# servis.net
KiCad netlist of a schematic drawn in EAGLE
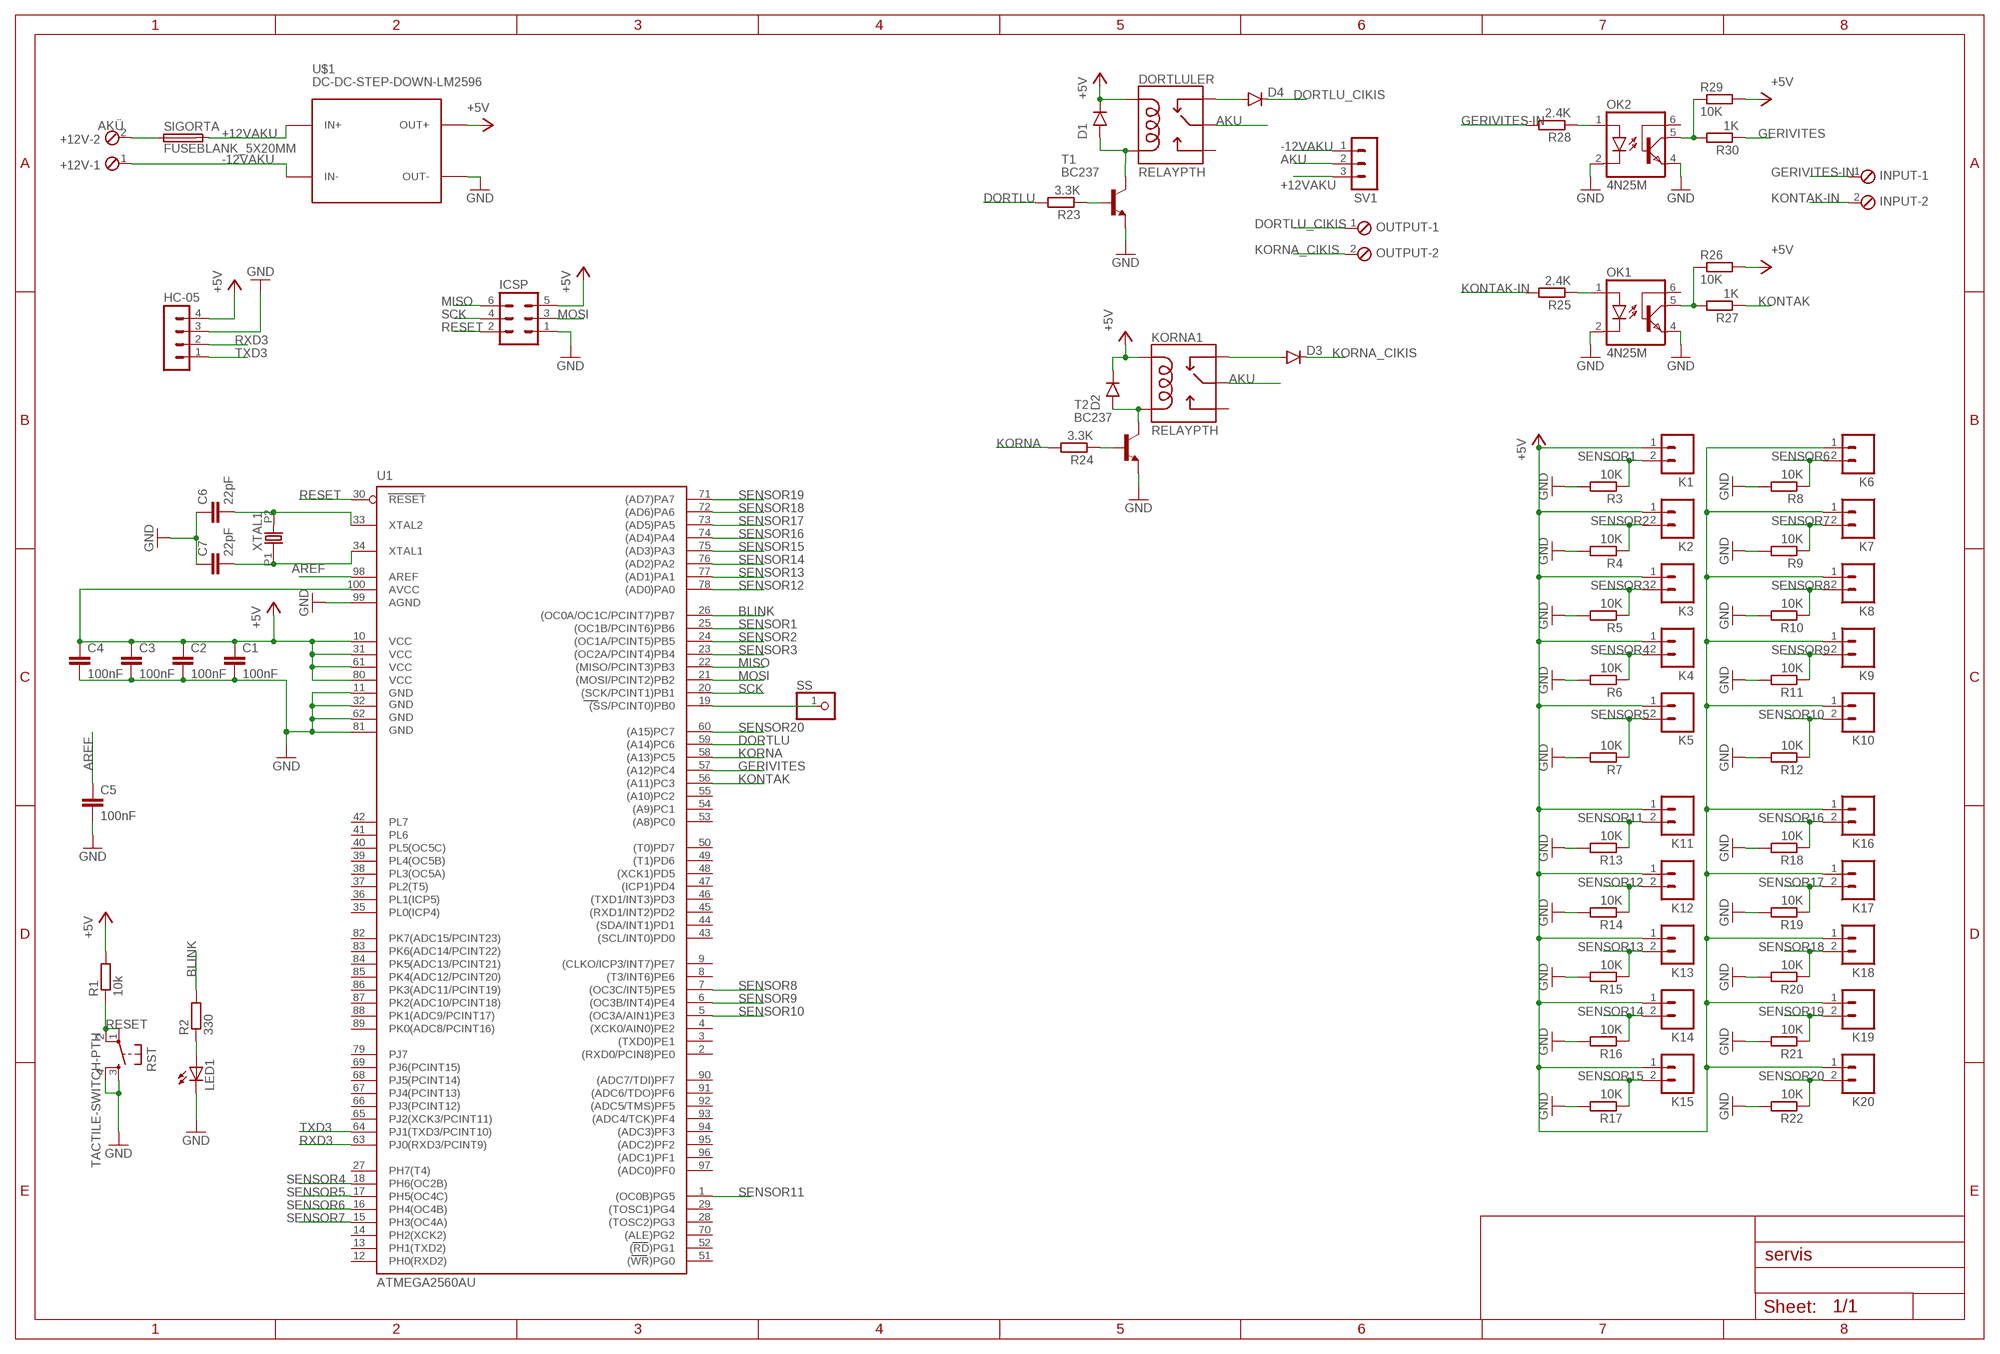
[diagram p0: schematic, sheet 1]

(export (version "E")
  (design (tool "Eeschema 10.0.6"))
  (components
    (comp (ref "+12V")
      (value "AKÜ")
      (footprint "eagle-import:2POL254")
      (libsource (lib "eagle-import") (part "MPT2"))
    )
    (comp (ref "C1")
      (value "100nF")
      (footprint "eagle-import:SPARKFUN_0805")
      (libsource (lib "eagle-import") (part "SPARKFUN_CAP0805"))
    )
    (comp (ref "C2")
      (value "100nF")
      (footprint "eagle-import:SPARKFUN_0805")
      (libsource (lib "eagle-import") (part "SPARKFUN_CAP0805"))
    )
    (comp (ref "C3")
      (value "100nF")
      (footprint "eagle-import:SPARKFUN_0805")
      (libsource (lib "eagle-import") (part "SPARKFUN_CAP0805"))
    )
    (comp (ref "C4")
      (value "100nF")
      (footprint "eagle-import:SPARKFUN_0805")
      (libsource (lib "eagle-import") (part "SPARKFUN_CAP0805"))
    )
    (comp (ref "C5")
      (value "100nF")
      (footprint "eagle-import:SPARKFUN_0805")
      (libsource (lib "eagle-import") (part "SPARKFUN_CAP0805"))
    )
    (comp (ref "C6")
      (value "22pF")
      (footprint "eagle-import:SPARKFUN_0805")
      (libsource (lib "eagle-import") (part "SPARKFUN_CAP0805"))
    )
    (comp (ref "C7")
      (value "22pF")
      (footprint "eagle-import:SPARKFUN_0805")
      (libsource (lib "eagle-import") (part "SPARKFUN_CAP0805"))
    )
    (comp (ref "D1")
      (value "1N4001")
      (footprint "eagle-import:DO41-10")
      (libsource (lib "eagle-import") (part "1N4001"))
    )
    (comp (ref "D2")
      (value "1N4001")
      (footprint "eagle-import:DO41-10")
      (libsource (lib "eagle-import") (part "1N4001"))
    )
    (comp (ref "D3")
      (value "DIODEPTH")
      (footprint "eagle-import:DIODE-1N4001")
      (libsource (lib "eagle-import") (part "DIODEPTH"))
    )
    (comp (ref "D4")
      (value "DIODEPTH")
      (footprint "eagle-import:DIODE-1N4001")
      (libsource (lib "eagle-import") (part "DIODEPTH"))
    )
    (comp (ref "DORTLULER")
      (value "RELAYPTH")
      (footprint "eagle-import:SRD-05VDC-SL-C")
      (libsource (lib "eagle-import") (part "RELAYPTH"))
    )
    (comp (ref "HC-05")
      (value "MA04-1")
      (footprint "eagle-import:MA04-1")
      (libsource (lib "eagle-import") (part "MA04-1"))
    )
    (comp (ref "ICSP")
      (value "MA03-2")
      (footprint "eagle-import:MA03-2")
      (libsource (lib "eagle-import") (part "MA03-2"))
    )
    (comp (ref "INPUT")
      (value "AKÜ")
      (footprint "eagle-import:2POL254")
      (libsource (lib "eagle-import") (part "MPT2"))
    )
    (comp (ref "K1")
      (value "SPARKFUN_M02-JST-2-PTH-NO_SILK")
      (footprint "eagle-import:SPARKFUN_JST-2-PTH-NS")
      (libsource (lib "eagle-import") (part "SPARKFUN_M02-JST-2-PTH-NO_SILK"))
    )
    (comp (ref "K2")
      (value "SPARKFUN_M02-JST-2-PTH-NO_SILK")
      (footprint "eagle-import:SPARKFUN_JST-2-PTH-NS")
      (libsource (lib "eagle-import") (part "SPARKFUN_M02-JST-2-PTH-NO_SILK"))
    )
    (comp (ref "K3")
      (value "SPARKFUN_M02-JST-2-PTH-NO_SILK")
      (footprint "eagle-import:SPARKFUN_JST-2-PTH-NS")
      (libsource (lib "eagle-import") (part "SPARKFUN_M02-JST-2-PTH-NO_SILK"))
    )
    (comp (ref "K4")
      (value "SPARKFUN_M02-JST-2-PTH-NO_SILK")
      (footprint "eagle-import:SPARKFUN_JST-2-PTH-NS")
      (libsource (lib "eagle-import") (part "SPARKFUN_M02-JST-2-PTH-NO_SILK"))
    )
    (comp (ref "K5")
      (value "SPARKFUN_M02-JST-2-PTH-NO_SILK")
      (footprint "eagle-import:SPARKFUN_JST-2-PTH-NS")
      (libsource (lib "eagle-import") (part "SPARKFUN_M02-JST-2-PTH-NO_SILK"))
    )
    (comp (ref "K6")
      (value "SPARKFUN_M02-JST-2-PTH-NO_SILK")
      (footprint "eagle-import:SPARKFUN_JST-2-PTH-NS")
      (libsource (lib "eagle-import") (part "SPARKFUN_M02-JST-2-PTH-NO_SILK"))
    )
    (comp (ref "K7")
      (value "SPARKFUN_M02-JST-2-PTH-NO_SILK")
      (footprint "eagle-import:SPARKFUN_JST-2-PTH-NS")
      (libsource (lib "eagle-import") (part "SPARKFUN_M02-JST-2-PTH-NO_SILK"))
    )
    (comp (ref "K8")
      (value "SPARKFUN_M02-JST-2-PTH-NO_SILK")
      (footprint "eagle-import:SPARKFUN_JST-2-PTH-NS")
      (libsource (lib "eagle-import") (part "SPARKFUN_M02-JST-2-PTH-NO_SILK"))
    )
    (comp (ref "K9")
      (value "SPARKFUN_M02-JST-2-PTH-NO_SILK")
      (footprint "eagle-import:SPARKFUN_JST-2-PTH-NS")
      (libsource (lib "eagle-import") (part "SPARKFUN_M02-JST-2-PTH-NO_SILK"))
    )
    (comp (ref "K10")
      (value "SPARKFUN_M02-JST-2-PTH-NO_SILK")
      (footprint "eagle-import:SPARKFUN_JST-2-PTH-NS")
      (libsource (lib "eagle-import") (part "SPARKFUN_M02-JST-2-PTH-NO_SILK"))
    )
    (comp (ref "K11")
      (value "SPARKFUN_M02-JST-2-PTH-NO_SILK")
      (footprint "eagle-import:SPARKFUN_JST-2-PTH-NS")
      (libsource (lib "eagle-import") (part "SPARKFUN_M02-JST-2-PTH-NO_SILK"))
    )
    (comp (ref "K12")
      (value "SPARKFUN_M02-JST-2-PTH-NO_SILK")
      (footprint "eagle-import:SPARKFUN_JST-2-PTH-NS")
      (libsource (lib "eagle-import") (part "SPARKFUN_M02-JST-2-PTH-NO_SILK"))
    )
    (comp (ref "K13")
      (value "SPARKFUN_M02-JST-2-PTH-NO_SILK")
      (footprint "eagle-import:SPARKFUN_JST-2-PTH-NS")
      (libsource (lib "eagle-import") (part "SPARKFUN_M02-JST-2-PTH-NO_SILK"))
    )
    (comp (ref "K14")
      (value "SPARKFUN_M02-JST-2-PTH-NO_SILK")
      (footprint "eagle-import:SPARKFUN_JST-2-PTH-NS")
      (libsource (lib "eagle-import") (part "SPARKFUN_M02-JST-2-PTH-NO_SILK"))
    )
    (comp (ref "K15")
      (value "SPARKFUN_M02-JST-2-PTH-NO_SILK")
      (footprint "eagle-import:SPARKFUN_JST-2-PTH-NS")
      (libsource (lib "eagle-import") (part "SPARKFUN_M02-JST-2-PTH-NO_SILK"))
    )
    (comp (ref "K16")
      (value "SPARKFUN_M02-JST-2-PTH-NO_SILK")
      (footprint "eagle-import:SPARKFUN_JST-2-PTH-NS")
      (libsource (lib "eagle-import") (part "SPARKFUN_M02-JST-2-PTH-NO_SILK"))
    )
    (comp (ref "K17")
      (value "SPARKFUN_M02-JST-2-PTH-NO_SILK")
      (footprint "eagle-import:SPARKFUN_JST-2-PTH-NS")
      (libsource (lib "eagle-import") (part "SPARKFUN_M02-JST-2-PTH-NO_SILK"))
    )
    (comp (ref "K18")
      (value "SPARKFUN_M02-JST-2-PTH-NO_SILK")
      (footprint "eagle-import:SPARKFUN_JST-2-PTH-NS")
      (libsource (lib "eagle-import") (part "SPARKFUN_M02-JST-2-PTH-NO_SILK"))
    )
    (comp (ref "K19")
      (value "SPARKFUN_M02-JST-2-PTH-NO_SILK")
      (footprint "eagle-import:SPARKFUN_JST-2-PTH-NS")
      (libsource (lib "eagle-import") (part "SPARKFUN_M02-JST-2-PTH-NO_SILK"))
    )
    (comp (ref "K20")
      (value "SPARKFUN_M02-JST-2-PTH-NO_SILK")
      (footprint "eagle-import:SPARKFUN_JST-2-PTH-NS")
      (libsource (lib "eagle-import") (part "SPARKFUN_M02-JST-2-PTH-NO_SILK"))
    )
    (comp (ref "KORNA1")
      (value "RELAYPTH")
      (footprint "eagle-import:SRD-05VDC-SL-C")
      (libsource (lib "eagle-import") (part "RELAYPTH"))
    )
    (comp (ref "LED1")
      (value "SPARKFUN_LED3MM")
      (footprint "eagle-import:SPARKFUN_LED3MM")
      (libsource (lib "eagle-import") (part "SPARKFUN_LED3MM"))
    )
    (comp (ref "OK1")
      (value "4N25M")
      (footprint "eagle-import:DIL06")
      (fields (field (name "MPN") "4N25-M"))
      (libsource (lib "eagle-import") (part "4N?M25"))
    )
    (comp (ref "OK2")
      (value "4N25M")
      (footprint "eagle-import:DIL06")
      (fields (field (name "MPN") "4N25-M"))
      (libsource (lib "eagle-import") (part "4N?M25"))
    )
    (comp (ref "OUTPUT")
      (value "AKÜ")
      (footprint "eagle-import:2POL254")
      (libsource (lib "eagle-import") (part "MPT2"))
    )
    (comp (ref "R1")
      (value "10k")
      (footprint "eagle-import:R805")
      (libsource (lib "eagle-import") (part "RESISTOR-0805R805"))
    )
    (comp (ref "R2")
      (value "330")
      (footprint "eagle-import:R805")
      (libsource (lib "eagle-import") (part "RESISTOR-0805R805"))
    )
    (comp (ref "R3")
      (value "10K")
      (footprint "eagle-import:R805")
      (libsource (lib "eagle-import") (part "RESISTOR-0805R805"))
    )
    (comp (ref "R4")
      (value "10K")
      (footprint "eagle-import:R805")
      (libsource (lib "eagle-import") (part "RESISTOR-0805R805"))
    )
    (comp (ref "R5")
      (value "10K")
      (footprint "eagle-import:R805")
      (libsource (lib "eagle-import") (part "RESISTOR-0805R805"))
    )
    (comp (ref "R6")
      (value "10K")
      (footprint "eagle-import:R805")
      (libsource (lib "eagle-import") (part "RESISTOR-0805R805"))
    )
    (comp (ref "R7")
      (value "10K")
      (footprint "eagle-import:R805")
      (libsource (lib "eagle-import") (part "RESISTOR-0805R805"))
    )
    (comp (ref "R8")
      (value "10K")
      (footprint "eagle-import:R805")
      (libsource (lib "eagle-import") (part "RESISTOR-0805R805"))
    )
    (comp (ref "R9")
      (value "10K")
      (footprint "eagle-import:R805")
      (libsource (lib "eagle-import") (part "RESISTOR-0805R805"))
    )
    (comp (ref "R10")
      (value "10K")
      (footprint "eagle-import:R805")
      (libsource (lib "eagle-import") (part "RESISTOR-0805R805"))
    )
    (comp (ref "R11")
      (value "10K")
      (footprint "eagle-import:R805")
      (libsource (lib "eagle-import") (part "RESISTOR-0805R805"))
    )
    (comp (ref "R12")
      (value "10K")
      (footprint "eagle-import:R805")
      (libsource (lib "eagle-import") (part "RESISTOR-0805R805"))
    )
    (comp (ref "R13")
      (value "10K")
      (footprint "eagle-import:R805")
      (libsource (lib "eagle-import") (part "RESISTOR-0805R805"))
    )
    (comp (ref "R14")
      (value "10K")
      (footprint "eagle-import:R805")
      (libsource (lib "eagle-import") (part "RESISTOR-0805R805"))
    )
    (comp (ref "R15")
      (value "10K")
      (footprint "eagle-import:R805")
      (libsource (lib "eagle-import") (part "RESISTOR-0805R805"))
    )
    (comp (ref "R16")
      (value "10K")
      (footprint "eagle-import:R805")
      (libsource (lib "eagle-import") (part "RESISTOR-0805R805"))
    )
    (comp (ref "R17")
      (value "10K")
      (footprint "eagle-import:R805")
      (libsource (lib "eagle-import") (part "RESISTOR-0805R805"))
    )
    (comp (ref "R18")
      (value "10K")
      (footprint "eagle-import:R805")
      (libsource (lib "eagle-import") (part "RESISTOR-0805R805"))
    )
    (comp (ref "R19")
      (value "10K")
      (footprint "eagle-import:R805")
      (libsource (lib "eagle-import") (part "RESISTOR-0805R805"))
    )
    (comp (ref "R20")
      (value "10K")
      (footprint "eagle-import:R805")
      (libsource (lib "eagle-import") (part "RESISTOR-0805R805"))
    )
    (comp (ref "R21")
      (value "10K")
      (footprint "eagle-import:R805")
      (libsource (lib "eagle-import") (part "RESISTOR-0805R805"))
    )
    (comp (ref "R22")
      (value "10K")
      (footprint "eagle-import:R805")
      (libsource (lib "eagle-import") (part "RESISTOR-0805R805"))
    )
    (comp (ref "R23")
      (value "3.3K")
      (footprint "eagle-import:R805")
      (libsource (lib "eagle-import") (part "RESISTOR-0805R805"))
    )
    (comp (ref "R24")
      (value "3.3K")
      (footprint "eagle-import:R805")
      (libsource (lib "eagle-import") (part "RESISTOR-0805R805"))
    )
    (comp (ref "R25")
      (value "2.4K")
      (footprint "eagle-import:R805")
      (libsource (lib "eagle-import") (part "RESISTOR-0805R805"))
    )
    (comp (ref "R26")
      (value "10K")
      (footprint "eagle-import:R805")
      (libsource (lib "eagle-import") (part "RESISTOR-0805R805"))
    )
    (comp (ref "R27")
      (value "1K")
      (footprint "eagle-import:R805")
      (libsource (lib "eagle-import") (part "RESISTOR-0805R805"))
    )
    (comp (ref "R28")
      (value "2.4K")
      (footprint "eagle-import:R805")
      (libsource (lib "eagle-import") (part "RESISTOR-0805R805"))
    )
    (comp (ref "R29")
      (value "10K")
      (footprint "eagle-import:R805")
      (libsource (lib "eagle-import") (part "RESISTOR-0805R805"))
    )
    (comp (ref "R30")
      (value "1K")
      (footprint "eagle-import:R805")
      (libsource (lib "eagle-import") (part "RESISTOR-0805R805"))
    )
    (comp (ref "RST")
      (value "TACTILE-SWITCH-PTH")
      (footprint "eagle-import:TAC-SWITCH-PTH")
      (libsource (lib "eagle-import") (part "TACTILE-SWITCH-PTH"))
    )
    (comp (ref "SIGORTA")
      (value "FUSEBLANK_5X20MM")
      (footprint "eagle-import:FUSE_HOLDER_5X20MM")
      (libsource (lib "eagle-import") (part "FUSEBLANK_5X20MM"))
    )
    (comp (ref "SS")
      (value "PINHD-1X1")
      (footprint "eagle-import:1X01")
      (libsource (lib "eagle-import") (part "PINHD-1X1"))
    )
    (comp (ref "SV1")
      (value "MA03-1")
      (footprint "eagle-import:MA03-1")
      (libsource (lib "eagle-import") (part "MA03-1"))
    )
    (comp (ref "T1")
      (value "BC237")
      (footprint "eagle-import:TO92")
      (libsource (lib "eagle-import") (part "BC237"))
    )
    (comp (ref "T2")
      (value "BC237")
      (footprint "eagle-import:TO92")
      (libsource (lib "eagle-import") (part "BC237"))
    )
    (comp (ref "U$1")
      (value "DC-DC-STEP-DOWN-LM2596")
      (footprint "eagle-import:DC-DC-STEP-DOWN-LM2596")
      (libsource (lib "eagle-import") (part "DC-DC-STEP-DOWN-LM2596"))
    )
    (comp (ref "U1")
      (value "ATMEGA2560AU")
      (footprint "eagle-import:TQFP100")
      (libsource (lib "eagle-import") (part "ATMEGA2560AU"))
    )
    (comp (ref "XTAL1")
      (value "OSC-XTAL-HC-49U-PTH")
      (footprint "eagle-import:HC-49U-PTH")
      (libsource (lib "eagle-import") (part "OSC-XTAL-HC-49U-PTH"))
    )
  )
  (nets
    (net (code "1") (name "+5V") (class "Default")
      (node (ref "C1") (pin "1") (pinfunction "1_1") (pintype "passive"))
      (node (ref "C2") (pin "1") (pinfunction "1_1") (pintype "passive"))
      (node (ref "C3") (pin "1") (pinfunction "1_1") (pintype "passive"))
      (node (ref "C4") (pin "1") (pinfunction "1_1") (pintype "passive"))
      (node (ref "D1") (pin "C") (pinfunction "CATHODE_C") (pintype "passive"))
      (node (ref "D2") (pin "C") (pinfunction "CATHODE_C") (pintype "passive"))
      (node (ref "DORTLULER") (pin "COIL1") (pinfunction "COIL1_COIL1") (pintype "bidirectional"))
      (node (ref "HC-05") (pin "4") (pinfunction "4_4") (pintype "passive"))
      (node (ref "ICSP") (pin "5") (pinfunction "5_5") (pintype "passive"))
      (node (ref "K1") (pin "1") (pinfunction "1_1") (pintype "passive"))
      (node (ref "K10") (pin "1") (pinfunction "1_1") (pintype "passive"))
      (node (ref "K11") (pin "1") (pinfunction "1_1") (pintype "passive"))
      (node (ref "K12") (pin "1") (pinfunction "1_1") (pintype "passive"))
      (node (ref "K13") (pin "1") (pinfunction "1_1") (pintype "passive"))
      (node (ref "K14") (pin "1") (pinfunction "1_1") (pintype "passive"))
      (node (ref "K15") (pin "1") (pinfunction "1_1") (pintype "passive"))
      (node (ref "K16") (pin "1") (pinfunction "1_1") (pintype "passive"))
      (node (ref "K17") (pin "1") (pinfunction "1_1") (pintype "passive"))
      (node (ref "K18") (pin "1") (pinfunction "1_1") (pintype "passive"))
      (node (ref "K19") (pin "1") (pinfunction "1_1") (pintype "passive"))
      (node (ref "K2") (pin "1") (pinfunction "1_1") (pintype "passive"))
      (node (ref "K20") (pin "1") (pinfunction "1_1") (pintype "passive"))
      (node (ref "K3") (pin "1") (pinfunction "1_1") (pintype "passive"))
      (node (ref "K4") (pin "1") (pinfunction "1_1") (pintype "passive"))
      (node (ref "K5") (pin "1") (pinfunction "1_1") (pintype "passive"))
      (node (ref "K6") (pin "1") (pinfunction "1_1") (pintype "passive"))
      (node (ref "K7") (pin "1") (pinfunction "1_1") (pintype "passive"))
      (node (ref "K8") (pin "1") (pinfunction "1_1") (pintype "passive"))
      (node (ref "K9") (pin "1") (pinfunction "1_1") (pintype "passive"))
      (node (ref "KORNA1") (pin "COIL1") (pinfunction "COIL1_COIL1") (pintype "bidirectional"))
      (node (ref "R1") (pin "2") (pinfunction "2_2") (pintype "passive"))
      (node (ref "R26") (pin "2") (pinfunction "2_2") (pintype "passive"))
      (node (ref "R29") (pin "2") (pinfunction "2_2") (pintype "passive"))
      (node (ref "U$1") (pin "OUT+") (pinfunction "OUT+_OUT+") (pintype "bidirectional"))
      (node (ref "U1") (pin "10") (pinfunction "VCC_10") (pintype "power_in"))
      (node (ref "U1") (pin "100") (pinfunction "AVCC_100") (pintype "power_in"))
      (node (ref "U1") (pin "31") (pinfunction "VCC1_31") (pintype "power_in"))
      (node (ref "U1") (pin "61") (pinfunction "VCC2_61") (pintype "power_in"))
      (node (ref "U1") (pin "80") (pinfunction "VCC3_80") (pintype "power_in"))
    )
    (net (code "2") (name "/+12VAKU") (class "Default")
      (node (ref "SIGORTA") (pin "2") (pinfunction "2_2") (pintype "passive"))
      (node (ref "SV1") (pin "3") (pinfunction "3_3") (pintype "passive"))
      (node (ref "U$1") (pin "IN+") (pinfunction "IN+_IN+") (pintype "bidirectional"))
    )
    (net (code "3") (name "/-12VAKU") (class "Default")
      (node (ref "+12V") (pin "1") (pinfunction "1_1") (pintype "passive"))
      (node (ref "SV1") (pin "1") (pinfunction "1_1") (pintype "passive"))
      (node (ref "U$1") (pin "IN-") (pinfunction "IN-_IN-") (pintype "bidirectional"))
    )
    (net (code "4") (name "/AKU") (class "Default")
      (node (ref "DORTLULER") (pin "SWCOMMON") (pinfunction "SWCOMMON_SWCOMMON") (pintype "bidirectional"))
      (node (ref "KORNA1") (pin "SWCOMMON") (pinfunction "SWCOMMON_SWCOMMON") (pintype "bidirectional"))
      (node (ref "SV1") (pin "2") (pinfunction "2_2") (pintype "passive"))
    )
    (net (code "5") (name "/AREF") (class "Default")
      (node (ref "C5") (pin "1") (pinfunction "1_1") (pintype "passive"))
      (node (ref "U1") (pin "98") (pinfunction "AREF_98") (pintype "bidirectional"))
    )
    (net (code "6") (name "/BLINK") (class "Default")
      (node (ref "R2") (pin "2") (pinfunction "2_2") (pintype "passive"))
      (node (ref "U1") (pin "26") (pinfunction "(OC0A/OC1C/PCINT7)PB7_26") (pintype "bidirectional"))
    )
    (net (code "7") (name "/DORTLU") (class "Default")
      (node (ref "R23") (pin "2") (pinfunction "2_2") (pintype "passive"))
      (node (ref "U1") (pin "59") (pinfunction "(A14)PC6_59") (pintype "bidirectional"))
    )
    (net (code "8") (name "/DORTLU_CIKIS") (class "Default")
      (node (ref "D4") (pin "C") (pinfunction "C_C") (pintype "passive"))
      (node (ref "OUTPUT") (pin "1") (pinfunction "1_1") (pintype "passive"))
    )
    (net (code "9") (name "/GERIVITES") (class "Default")
      (node (ref "R30") (pin "1") (pinfunction "1_1") (pintype "passive"))
      (node (ref "U1") (pin "57") (pinfunction "(A12)PC4_57") (pintype "bidirectional"))
    )
    (net (code "10") (name "/GERIVITES-IN") (class "Default")
      (node (ref "INPUT") (pin "1") (pinfunction "1_1") (pintype "passive"))
      (node (ref "R28") (pin "2") (pinfunction "2_2") (pintype "passive"))
    )
    (net (code "11") (name "/KONTAK") (class "Default")
      (node (ref "R27") (pin "1") (pinfunction "1_1") (pintype "passive"))
      (node (ref "U1") (pin "56") (pinfunction "(A11)PC3_56") (pintype "bidirectional"))
    )
    (net (code "12") (name "/KONTAK-IN") (class "Default")
      (node (ref "INPUT") (pin "2") (pinfunction "1_2") (pintype "passive"))
      (node (ref "R25") (pin "2") (pinfunction "2_2") (pintype "passive"))
    )
    (net (code "13") (name "/KORNA") (class "Default")
      (node (ref "R24") (pin "2") (pinfunction "2_2") (pintype "passive"))
      (node (ref "U1") (pin "58") (pinfunction "(A13)PC5_58") (pintype "bidirectional"))
    )
    (net (code "14") (name "/KORNA_CIKIS") (class "Default")
      (node (ref "D3") (pin "C") (pinfunction "C_C") (pintype "passive"))
      (node (ref "OUTPUT") (pin "2") (pinfunction "1_2") (pintype "passive"))
    )
    (net (code "15") (name "/MISO") (class "Default")
      (node (ref "ICSP") (pin "6") (pinfunction "6_6") (pintype "passive"))
      (node (ref "U1") (pin "22") (pinfunction "(MISO/PCINT3)PB3_22") (pintype "bidirectional"))
    )
    (net (code "16") (name "/MOSI") (class "Default")
      (node (ref "ICSP") (pin "3") (pinfunction "3_3") (pintype "passive"))
      (node (ref "U1") (pin "21") (pinfunction "(MOSI/PCINT2)PB2_21") (pintype "bidirectional"))
    )
    (net (code "17") (name "/RESET") (class "Default")
      (node (ref "ICSP") (pin "2") (pinfunction "2_2") (pintype "passive"))
      (node (ref "R1") (pin "1") (pinfunction "1_1") (pintype "passive"))
      (node (ref "RST") (pin "1") (pinfunction "1_1") (pintype "passive"))
      (node (ref "RST") (pin "2") (pinfunction "2_2") (pintype "passive"))
      (node (ref "U1") (pin "30") (pinfunction "RESET_30") (pintype "input"))
    )
    (net (code "18") (name "/RXD3") (class "Default")
      (node (ref "HC-05") (pin "2") (pinfunction "2_2") (pintype "passive"))
      (node (ref "U1") (pin "63") (pinfunction "PJ0(RXD3/PCINT9)_63") (pintype "bidirectional"))
    )
    (net (code "19") (name "/SCK") (class "Default")
      (node (ref "ICSP") (pin "4") (pinfunction "4_4") (pintype "passive"))
      (node (ref "U1") (pin "20") (pinfunction "(SCK/PCINT1)PB1_20") (pintype "bidirectional"))
    )
    (net (code "20") (name "/SENSOR1") (class "Default")
      (node (ref "K1") (pin "2") (pinfunction "2_2") (pintype "passive"))
      (node (ref "R3") (pin "1") (pinfunction "1_1") (pintype "passive"))
      (node (ref "U1") (pin "25") (pinfunction "(OC1B/PCINT6)PB6_25") (pintype "bidirectional"))
    )
    (net (code "21") (name "/SENSOR2") (class "Default")
      (node (ref "K2") (pin "2") (pinfunction "2_2") (pintype "passive"))
      (node (ref "R4") (pin "1") (pinfunction "1_1") (pintype "passive"))
      (node (ref "U1") (pin "24") (pinfunction "(OC1A/PCINT5)PB5_24") (pintype "bidirectional"))
    )
    (net (code "22") (name "/SENSOR3") (class "Default")
      (node (ref "K3") (pin "2") (pinfunction "2_2") (pintype "passive"))
      (node (ref "R5") (pin "1") (pinfunction "1_1") (pintype "passive"))
      (node (ref "U1") (pin "23") (pinfunction "(OC2A/PCINT4)PB4_23") (pintype "bidirectional"))
    )
    (net (code "23") (name "/SENSOR4") (class "Default")
      (node (ref "K4") (pin "2") (pinfunction "2_2") (pintype "passive"))
      (node (ref "R6") (pin "1") (pinfunction "1_1") (pintype "passive"))
      (node (ref "U1") (pin "18") (pinfunction "PH6(OC2B)_18") (pintype "bidirectional"))
    )
    (net (code "24") (name "/SENSOR5") (class "Default")
      (node (ref "K5") (pin "2") (pinfunction "2_2") (pintype "passive"))
      (node (ref "R7") (pin "1") (pinfunction "1_1") (pintype "passive"))
      (node (ref "U1") (pin "17") (pinfunction "PH5(OC4C)_17") (pintype "bidirectional"))
    )
    (net (code "25") (name "/SENSOR6") (class "Default")
      (node (ref "K6") (pin "2") (pinfunction "2_2") (pintype "passive"))
      (node (ref "R8") (pin "1") (pinfunction "1_1") (pintype "passive"))
      (node (ref "U1") (pin "16") (pinfunction "PH4(OC4B)_16") (pintype "bidirectional"))
    )
    (net (code "26") (name "/SENSOR7") (class "Default")
      (node (ref "K7") (pin "2") (pinfunction "2_2") (pintype "passive"))
      (node (ref "R9") (pin "1") (pinfunction "1_1") (pintype "passive"))
      (node (ref "U1") (pin "15") (pinfunction "PH3(OC4A)_15") (pintype "bidirectional"))
    )
    (net (code "27") (name "/SENSOR8") (class "Default")
      (node (ref "K8") (pin "2") (pinfunction "2_2") (pintype "passive"))
      (node (ref "R10") (pin "1") (pinfunction "1_1") (pintype "passive"))
      (node (ref "U1") (pin "7") (pinfunction "(OC3C/INT5)PE5_7") (pintype "bidirectional"))
    )
    (net (code "28") (name "/SENSOR9") (class "Default")
      (node (ref "K9") (pin "2") (pinfunction "2_2") (pintype "passive"))
      (node (ref "R11") (pin "1") (pinfunction "1_1") (pintype "passive"))
      (node (ref "U1") (pin "6") (pinfunction "(OC3B/INT4)PE4_6") (pintype "bidirectional"))
    )
    (net (code "29") (name "/SENSOR10") (class "Default")
      (node (ref "K10") (pin "2") (pinfunction "2_2") (pintype "passive"))
      (node (ref "R12") (pin "1") (pinfunction "1_1") (pintype "passive"))
      (node (ref "U1") (pin "5") (pinfunction "(OC3A/AIN1)PE3_5") (pintype "bidirectional"))
    )
    (net (code "30") (name "/SENSOR11") (class "Default")
      (node (ref "K11") (pin "2") (pinfunction "2_2") (pintype "passive"))
      (node (ref "R13") (pin "1") (pinfunction "1_1") (pintype "passive"))
      (node (ref "U1") (pin "1") (pinfunction "(OC0B)PG5_1") (pintype "bidirectional"))
    )
    (net (code "31") (name "/SENSOR12") (class "Default")
      (node (ref "K12") (pin "2") (pinfunction "2_2") (pintype "passive"))
      (node (ref "R14") (pin "1") (pinfunction "1_1") (pintype "passive"))
      (node (ref "U1") (pin "78") (pinfunction "(AD0)PA0_78") (pintype "bidirectional"))
    )
    (net (code "32") (name "/SENSOR13") (class "Default")
      (node (ref "K13") (pin "2") (pinfunction "2_2") (pintype "passive"))
      (node (ref "R15") (pin "1") (pinfunction "1_1") (pintype "passive"))
      (node (ref "U1") (pin "77") (pinfunction "(AD1)PA1_77") (pintype "bidirectional"))
    )
    (net (code "33") (name "/SENSOR14") (class "Default")
      (node (ref "K14") (pin "2") (pinfunction "2_2") (pintype "passive"))
      (node (ref "R16") (pin "1") (pinfunction "1_1") (pintype "passive"))
      (node (ref "U1") (pin "76") (pinfunction "(AD2)PA2_76") (pintype "bidirectional"))
    )
    (net (code "34") (name "/SENSOR15") (class "Default")
      (node (ref "K15") (pin "2") (pinfunction "2_2") (pintype "passive"))
      (node (ref "R17") (pin "1") (pinfunction "1_1") (pintype "passive"))
      (node (ref "U1") (pin "75") (pinfunction "(AD3)PA3_75") (pintype "bidirectional"))
    )
    (net (code "35") (name "/SENSOR16") (class "Default")
      (node (ref "K16") (pin "2") (pinfunction "2_2") (pintype "passive"))
      (node (ref "R18") (pin "1") (pinfunction "1_1") (pintype "passive"))
      (node (ref "U1") (pin "74") (pinfunction "(AD4)PA4_74") (pintype "bidirectional"))
    )
    (net (code "36") (name "/SENSOR17") (class "Default")
      (node (ref "K17") (pin "2") (pinfunction "2_2") (pintype "passive"))
      (node (ref "R19") (pin "1") (pinfunction "1_1") (pintype "passive"))
      (node (ref "U1") (pin "73") (pinfunction "(AD5)PA5_73") (pintype "bidirectional"))
    )
    (net (code "37") (name "/SENSOR18") (class "Default")
      (node (ref "K18") (pin "2") (pinfunction "2_2") (pintype "passive"))
      (node (ref "R20") (pin "1") (pinfunction "1_1") (pintype "passive"))
      (node (ref "U1") (pin "72") (pinfunction "(AD6)PA6_72") (pintype "bidirectional"))
    )
    (net (code "38") (name "/SENSOR19") (class "Default")
      (node (ref "K19") (pin "2") (pinfunction "2_2") (pintype "passive"))
      (node (ref "R21") (pin "1") (pinfunction "1_1") (pintype "passive"))
      (node (ref "U1") (pin "71") (pinfunction "(AD7)PA7_71") (pintype "bidirectional"))
    )
    (net (code "39") (name "/SENSOR20") (class "Default")
      (node (ref "K20") (pin "2") (pinfunction "2_2") (pintype "passive"))
      (node (ref "R22") (pin "1") (pinfunction "1_1") (pintype "passive"))
      (node (ref "U1") (pin "60") (pinfunction "(A15)PC7_60") (pintype "bidirectional"))
    )
    (net (code "40") (name "/TXD3") (class "Default")
      (node (ref "HC-05") (pin "1") (pinfunction "1_1") (pintype "passive"))
      (node (ref "U1") (pin "64") (pinfunction "PJ1(TXD3/PCINT10)_64") (pintype "bidirectional"))
    )
    (net (code "41") (name "GND") (class "Default")
      (node (ref "C1") (pin "2") (pinfunction "2_2") (pintype "passive"))
      (node (ref "C2") (pin "2") (pinfunction "2_2") (pintype "passive"))
      (node (ref "C3") (pin "2") (pinfunction "2_2") (pintype "passive"))
      (node (ref "C4") (pin "2") (pinfunction "2_2") (pintype "passive"))
      (node (ref "C5") (pin "2") (pinfunction "2_2") (pintype "passive"))
      (node (ref "C6") (pin "1") (pinfunction "1_1") (pintype "passive"))
      (node (ref "C7") (pin "1") (pinfunction "1_1") (pintype "passive"))
      (node (ref "HC-05") (pin "3") (pinfunction "3_3") (pintype "passive"))
      (node (ref "ICSP") (pin "1") (pinfunction "1_1") (pintype "passive"))
      (node (ref "LED1") (pin "K") (pinfunction "C_K") (pintype "passive"))
      (node (ref "OK1") (pin "2") (pinfunction "C_2") (pintype "passive"))
      (node (ref "OK1") (pin "4") (pinfunction "EMI_4") (pintype "passive"))
      (node (ref "OK2") (pin "2") (pinfunction "C_2") (pintype "passive"))
      (node (ref "OK2") (pin "4") (pinfunction "EMI_4") (pintype "passive"))
      (node (ref "R10") (pin "2") (pinfunction "2_2") (pintype "passive"))
      (node (ref "R11") (pin "2") (pinfunction "2_2") (pintype "passive"))
      (node (ref "R12") (pin "2") (pinfunction "2_2") (pintype "passive"))
      (node (ref "R13") (pin "2") (pinfunction "2_2") (pintype "passive"))
      (node (ref "R14") (pin "2") (pinfunction "2_2") (pintype "passive"))
      (node (ref "R15") (pin "2") (pinfunction "2_2") (pintype "passive"))
      (node (ref "R16") (pin "2") (pinfunction "2_2") (pintype "passive"))
      (node (ref "R17") (pin "2") (pinfunction "2_2") (pintype "passive"))
      (node (ref "R18") (pin "2") (pinfunction "2_2") (pintype "passive"))
      (node (ref "R19") (pin "2") (pinfunction "2_2") (pintype "passive"))
      (node (ref "R20") (pin "2") (pinfunction "2_2") (pintype "passive"))
      (node (ref "R21") (pin "2") (pinfunction "2_2") (pintype "passive"))
      (node (ref "R22") (pin "2") (pinfunction "2_2") (pintype "passive"))
      (node (ref "R3") (pin "2") (pinfunction "2_2") (pintype "passive"))
      (node (ref "R4") (pin "2") (pinfunction "2_2") (pintype "passive"))
      (node (ref "R5") (pin "2") (pinfunction "2_2") (pintype "passive"))
      (node (ref "R6") (pin "2") (pinfunction "2_2") (pintype "passive"))
      (node (ref "R7") (pin "2") (pinfunction "2_2") (pintype "passive"))
      (node (ref "R8") (pin "2") (pinfunction "2_2") (pintype "passive"))
      (node (ref "R9") (pin "2") (pinfunction "2_2") (pintype "passive"))
      (node (ref "RST") (pin "3") (pinfunction "3_3") (pintype "passive"))
      (node (ref "RST") (pin "4") (pinfunction "4_4") (pintype "passive"))
      (node (ref "T1") (pin "1") (pinfunction "E_1") (pintype "passive"))
      (node (ref "T2") (pin "1") (pinfunction "E_1") (pintype "passive"))
      (node (ref "U$1") (pin "OUT-") (pinfunction "OUT-_OUT-") (pintype "bidirectional"))
      (node (ref "U1") (pin "11") (pinfunction "GND_11") (pintype "power_in"))
      (node (ref "U1") (pin "32") (pinfunction "GND1_32") (pintype "power_in"))
      (node (ref "U1") (pin "62") (pinfunction "GND2_62") (pintype "power_in"))
      (node (ref "U1") (pin "81") (pinfunction "GND3_81") (pintype "power_in"))
      (node (ref "U1") (pin "99") (pinfunction "AGND_99") (pintype "power_in"))
    )
    (net (code "42") (name "Net-(+12VB-1)") (class "Default")
      (node (ref "+12V") (pin "2") (pinfunction "1_2") (pintype "passive"))
      (node (ref "SIGORTA") (pin "1") (pinfunction "1_1") (pintype "passive"))
    )
    (net (code "43") (name "Net-(D1-ANODE)") (class "Default")
      (node (ref "D1") (pin "A") (pinfunction "ANODE_A") (pintype "passive"))
      (node (ref "DORTLULER") (pin "COIL0") (pinfunction "COIL0_COIL0") (pintype "bidirectional"))
      (node (ref "T1") (pin "3") (pinfunction "C_3") (pintype "passive"))
    )
    (net (code "44") (name "Net-(D2-ANODE)") (class "Default")
      (node (ref "D2") (pin "A") (pinfunction "ANODE_A") (pintype "passive"))
      (node (ref "KORNA1") (pin "COIL0") (pinfunction "COIL0_COIL0") (pintype "bidirectional"))
      (node (ref "T2") (pin "3") (pinfunction "C_3") (pintype "passive"))
    )
    (net (code "45") (name "Net-(DORTLULER-SWCLOSE)") (class "Default")
      (node (ref "D4") (pin "A") (pinfunction "A_A") (pintype "passive"))
      (node (ref "DORTLULER") (pin "SWCLOSED") (pinfunction "SWCLOSE_SWCLOSED") (pintype "bidirectional"))
    )
    (net (code "46") (name "Net-(KORNA1-SWCLOSE)") (class "Default")
      (node (ref "D3") (pin "A") (pinfunction "A_A") (pintype "passive"))
      (node (ref "KORNA1") (pin "SWCLOSED") (pinfunction "SWCLOSE_SWCLOSED") (pintype "bidirectional"))
    )
    (net (code "47") (name "Net-(LED1-PadA)") (class "Default")
      (node (ref "LED1") (pin "A") (pinfunction "A_A") (pintype "passive"))
      (node (ref "R2") (pin "1") (pinfunction "1_1") (pintype "passive"))
    )
    (net (code "48") (name "Net-(OK1-A)") (class "Default")
      (node (ref "OK1") (pin "1") (pinfunction "A_1") (pintype "passive"))
      (node (ref "R25") (pin "1") (pinfunction "1_1") (pintype "passive"))
    )
    (net (code "49") (name "Net-(OK1-COL)") (class "Default")
      (node (ref "OK1") (pin "5") (pinfunction "COL_5") (pintype "passive"))
      (node (ref "R26") (pin "1") (pinfunction "1_1") (pintype "passive"))
      (node (ref "R27") (pin "2") (pinfunction "2_2") (pintype "passive"))
    )
    (net (code "50") (name "Net-(OK2-A)") (class "Default")
      (node (ref "OK2") (pin "1") (pinfunction "A_1") (pintype "passive"))
      (node (ref "R28") (pin "1") (pinfunction "1_1") (pintype "passive"))
    )
    (net (code "51") (name "Net-(OK2-COL)") (class "Default")
      (node (ref "OK2") (pin "5") (pinfunction "COL_5") (pintype "passive"))
      (node (ref "R29") (pin "1") (pinfunction "1_1") (pintype "passive"))
      (node (ref "R30") (pin "2") (pinfunction "2_2") (pintype "passive"))
    )
    (net (code "52") (name "Net-(T1-B)") (class "Default")
      (node (ref "R23") (pin "1") (pinfunction "1_1") (pintype "passive"))
      (node (ref "T1") (pin "2") (pinfunction "B_2") (pintype "passive"))
    )
    (net (code "53") (name "Net-(T2-B)") (class "Default")
      (node (ref "R24") (pin "1") (pinfunction "1_1") (pintype "passive"))
      (node (ref "T2") (pin "2") (pinfunction "B_2") (pintype "passive"))
    )
    (net (code "54") (name "Net-(U1-(SS{slash}PCINT0)PB0)") (class "Default")
      (node (ref "SS") (pin "1") (pinfunction "1_1") (pintype "passive"))
      (node (ref "U1") (pin "19") (pinfunction "(SS/PCINT0)PB0_19") (pintype "bidirectional"))
    )
    (net (code "55") (name "Net-(U1-XTAL1)") (class "Default")
      (node (ref "C7") (pin "2") (pinfunction "2_2") (pintype "passive"))
      (node (ref "U1") (pin "34") (pinfunction "XTAL1_34") (pintype "input"))
      (node (ref "XTAL1") (pin "P1") (pinfunction "1_P1") (pintype "passive"))
    )
    (net (code "56") (name "Net-(U1-XTAL2)") (class "Default")
      (node (ref "C6") (pin "2") (pinfunction "2_2") (pintype "passive"))
      (node (ref "U1") (pin "33") (pinfunction "XTAL2_33") (pintype "output"))
      (node (ref "XTAL1") (pin "P2") (pinfunction "2_P2") (pintype "passive"))
    )
    (net (code "57") (name "unconnected-(DORTLULER-PadSWOPEN)") (class "Default")
      (node (ref "DORTLULER") (pin "SWOPEN") (pinfunction "SWOPEN_SWOPEN") (pintype "bidirectional"))
    )
    (net (code "58") (name "unconnected-(KORNA1-PadSWOPEN)") (class "Default")
      (node (ref "KORNA1") (pin "SWOPEN") (pinfunction "SWOPEN_SWOPEN") (pintype "bidirectional"))
    )
    (net (code "59") (name "unconnected-(OK1-BAS-Pad6)") (class "Default")
      (node (ref "OK1") (pin "6") (pinfunction "BAS_6") (pintype "passive"))
    )
    (net (code "60") (name "unconnected-(OK2-BAS-Pad6)") (class "Default")
      (node (ref "OK2") (pin "6") (pinfunction "BAS_6") (pintype "passive"))
    )
    (net (code "61") (name "unconnected-(U1-(A8)PC0-Pad53)") (class "Default")
      (node (ref "U1") (pin "53") (pinfunction "(A8)PC0_53") (pintype "bidirectional"))
    )
    (net (code "62") (name "unconnected-(U1-(A9)PC1-Pad54)") (class "Default")
      (node (ref "U1") (pin "54") (pinfunction "(A9)PC1_54") (pintype "bidirectional"))
    )
    (net (code "63") (name "unconnected-(U1-(A10)PC2-Pad55)") (class "Default")
      (node (ref "U1") (pin "55") (pinfunction "(A10)PC2_55") (pintype "bidirectional"))
    )
    (net (code "64") (name "unconnected-(U1-(ADC0)PF0-Pad97)") (class "Default")
      (node (ref "U1") (pin "97") (pinfunction "(ADC0)PF0_97") (pintype "bidirectional"))
    )
    (net (code "65") (name "unconnected-(U1-(ADC1)PF1-Pad96)") (class "Default")
      (node (ref "U1") (pin "96") (pinfunction "(ADC1)PF1_96") (pintype "bidirectional"))
    )
    (net (code "66") (name "unconnected-(U1-(ADC2)PF2-Pad95)") (class "Default")
      (node (ref "U1") (pin "95") (pinfunction "(ADC2)PF2_95") (pintype "bidirectional"))
    )
    (net (code "67") (name "unconnected-(U1-(ADC3)PF3-Pad94)") (class "Default")
      (node (ref "U1") (pin "94") (pinfunction "(ADC3)PF3_94") (pintype "bidirectional"))
    )
    (net (code "68") (name "unconnected-(U1-(ADC4{slash}TCK)PF4-Pad93)") (class "Default")
      (node (ref "U1") (pin "93") (pinfunction "(ADC4/TCK)PF4_93") (pintype "bidirectional"))
    )
    (net (code "69") (name "unconnected-(U1-(ADC5{slash}TMS)PF5-Pad92)") (class "Default")
      (node (ref "U1") (pin "92") (pinfunction "(ADC5/TMS)PF5_92") (pintype "bidirectional"))
    )
    (net (code "70") (name "unconnected-(U1-(ADC6{slash}TDO)PF6-Pad91)") (class "Default")
      (node (ref "U1") (pin "91") (pinfunction "(ADC6/TDO)PF6_91") (pintype "bidirectional"))
    )
    (net (code "71") (name "unconnected-(U1-(ADC7{slash}TDI)PF7-Pad90)") (class "Default")
      (node (ref "U1") (pin "90") (pinfunction "(ADC7/TDI)PF7_90") (pintype "bidirectional"))
    )
    (net (code "72") (name "unconnected-(U1-(ALE)PG2-Pad70)") (class "Default")
      (node (ref "U1") (pin "70") (pinfunction "(ALE)PG2_70") (pintype "bidirectional"))
    )
    (net (code "73") (name "unconnected-(U1-(CLKO{slash}ICP3{slash}INT7)PE7-Pad9)") (class "Default")
      (node (ref "U1") (pin "9") (pinfunction "(CLKO/ICP3/INT7)PE7_9") (pintype "bidirectional"))
    )
    (net (code "74") (name "unconnected-(U1-(ICP1)PD4-Pad47)") (class "Default")
      (node (ref "U1") (pin "47") (pinfunction "(ICP1)PD4_47") (pintype "bidirectional"))
    )
    (net (code "75") (name "unconnected-(U1-(RD)PG1-Pad52)") (class "Default")
      (node (ref "U1") (pin "52") (pinfunction "(RD)PG1_52") (pintype "bidirectional"))
    )
    (net (code "76") (name "unconnected-(U1-(RXD0{slash}PCIN8)PE0-Pad2)") (class "Default")
      (node (ref "U1") (pin "2") (pinfunction "(RXD0/PCIN8)PE0_2") (pintype "bidirectional"))
    )
    (net (code "77") (name "unconnected-(U1-(RXD1{slash}INT2)PD2-Pad45)") (class "Default")
      (node (ref "U1") (pin "45") (pinfunction "(RXD1/INT2)PD2_45") (pintype "bidirectional"))
    )
    (net (code "78") (name "unconnected-(U1-(SCL{slash}INT0)PD0-Pad43)") (class "Default")
      (node (ref "U1") (pin "43") (pinfunction "(SCL/INT0)PD0_43") (pintype "bidirectional"))
    )
    (net (code "79") (name "unconnected-(U1-(SDA{slash}INT1)PD1-Pad44)") (class "Default")
      (node (ref "U1") (pin "44") (pinfunction "(SDA/INT1)PD1_44") (pintype "bidirectional"))
    )
    (net (code "80") (name "unconnected-(U1-(T0)PD7-Pad50)") (class "Default")
      (node (ref "U1") (pin "50") (pinfunction "(T0)PD7_50") (pintype "bidirectional"))
    )
    (net (code "81") (name "unconnected-(U1-(T1)PD6-Pad49)") (class "Default")
      (node (ref "U1") (pin "49") (pinfunction "(T1)PD6_49") (pintype "bidirectional"))
    )
    (net (code "82") (name "unconnected-(U1-(T3{slash}INT6)PE6-Pad8)") (class "Default")
      (node (ref "U1") (pin "8") (pinfunction "(T3/INT6)PE6_8") (pintype "bidirectional"))
    )
    (net (code "83") (name "unconnected-(U1-(TOSC1)PG4-Pad29)") (class "Default")
      (node (ref "U1") (pin "29") (pinfunction "(TOSC1)PG4_29") (pintype "bidirectional"))
    )
    (net (code "84") (name "unconnected-(U1-(TOSC2)PG3-Pad28)") (class "Default")
      (node (ref "U1") (pin "28") (pinfunction "(TOSC2)PG3_28") (pintype "bidirectional"))
    )
    (net (code "85") (name "unconnected-(U1-(TXD0)PE1-Pad3)") (class "Default")
      (node (ref "U1") (pin "3") (pinfunction "(TXD0)PE1_3") (pintype "bidirectional"))
    )
    (net (code "86") (name "unconnected-(U1-(TXD1{slash}INT3)PD3-Pad46)") (class "Default")
      (node (ref "U1") (pin "46") (pinfunction "(TXD1/INT3)PD3_46") (pintype "bidirectional"))
    )
    (net (code "87") (name "unconnected-(U1-(WR)PG0-Pad51)") (class "Default")
      (node (ref "U1") (pin "51") (pinfunction "(WR)PG0_51") (pintype "bidirectional"))
    )
    (net (code "88") (name "unconnected-(U1-(XCK0{slash}AIN0)PE2-Pad4)") (class "Default")
      (node (ref "U1") (pin "4") (pinfunction "(XCK0/AIN0)PE2_4") (pintype "bidirectional"))
    )
    (net (code "89") (name "unconnected-(U1-(XCK1)PD5-Pad48)") (class "Default")
      (node (ref "U1") (pin "48") (pinfunction "(XCK1)PD5_48") (pintype "bidirectional"))
    )
    (net (code "90") (name "unconnected-(U1-PH0(RXD2)-Pad12)") (class "Default")
      (node (ref "U1") (pin "12") (pinfunction "PH0(RXD2)_12") (pintype "bidirectional"))
    )
    (net (code "91") (name "unconnected-(U1-PH1(TXD2)-Pad13)") (class "Default")
      (node (ref "U1") (pin "13") (pinfunction "PH1(TXD2)_13") (pintype "bidirectional"))
    )
    (net (code "92") (name "unconnected-(U1-PH2(XCK2)-Pad14)") (class "Default")
      (node (ref "U1") (pin "14") (pinfunction "PH2(XCK2)_14") (pintype "bidirectional"))
    )
    (net (code "93") (name "unconnected-(U1-PH7(T4)-Pad27)") (class "Default")
      (node (ref "U1") (pin "27") (pinfunction "PH7(T4)_27") (pintype "bidirectional"))
    )
    (net (code "94") (name "unconnected-(U1-PJ2(XCK3{slash}PCINT11)-Pad65)") (class "Default")
      (node (ref "U1") (pin "65") (pinfunction "PJ2(XCK3/PCINT11)_65") (pintype "bidirectional"))
    )
    (net (code "95") (name "unconnected-(U1-PJ3(PCINT12)-Pad66)") (class "Default")
      (node (ref "U1") (pin "66") (pinfunction "PJ3(PCINT12)_66") (pintype "bidirectional"))
    )
    (net (code "96") (name "unconnected-(U1-PJ4(PCINT13)-Pad67)") (class "Default")
      (node (ref "U1") (pin "67") (pinfunction "PJ4(PCINT13)_67") (pintype "bidirectional"))
    )
    (net (code "97") (name "unconnected-(U1-PJ5(PCINT14)-Pad68)") (class "Default")
      (node (ref "U1") (pin "68") (pinfunction "PJ5(PCINT14)_68") (pintype "bidirectional"))
    )
    (net (code "98") (name "unconnected-(U1-PJ6(PCINT15)-Pad69)") (class "Default")
      (node (ref "U1") (pin "69") (pinfunction "PJ6(PCINT15)_69") (pintype "bidirectional"))
    )
    (net (code "99") (name "unconnected-(U1-PJ7-Pad79)") (class "Default")
      (node (ref "U1") (pin "79") (pinfunction "PJ7_79") (pintype "bidirectional"))
    )
    (net (code "100") (name "unconnected-(U1-PK0(ADC8{slash}PCINT16)-Pad89)") (class "Default")
      (node (ref "U1") (pin "89") (pinfunction "PK0(ADC8/PCINT16)_89") (pintype "bidirectional"))
    )
    (net (code "101") (name "unconnected-(U1-PK1(ADC9{slash}PCINT17)-Pad88)") (class "Default")
      (node (ref "U1") (pin "88") (pinfunction "PK1(ADC9/PCINT17)_88") (pintype "bidirectional"))
    )
    (net (code "102") (name "unconnected-(U1-PK2(ADC10{slash}PCINT18)-Pad87)") (class "Default")
      (node (ref "U1") (pin "87") (pinfunction "PK2(ADC10/PCINT18)_87") (pintype "bidirectional"))
    )
    (net (code "103") (name "unconnected-(U1-PK3(ADC11{slash}PCINT19)-Pad86)") (class "Default")
      (node (ref "U1") (pin "86") (pinfunction "PK3(ADC11/PCINT19)_86") (pintype "bidirectional"))
    )
    (net (code "104") (name "unconnected-(U1-PK4(ADC12{slash}PCINT20)-Pad85)") (class "Default")
      (node (ref "U1") (pin "85") (pinfunction "PK4(ADC12/PCINT20)_85") (pintype "bidirectional"))
    )
    (net (code "105") (name "unconnected-(U1-PK5(ADC13{slash}PCINT21)-Pad84)") (class "Default")
      (node (ref "U1") (pin "84") (pinfunction "PK5(ADC13/PCINT21)_84") (pintype "bidirectional"))
    )
    (net (code "106") (name "unconnected-(U1-PK6(ADC14{slash}PCINT22)-Pad83)") (class "Default")
      (node (ref "U1") (pin "83") (pinfunction "PK6(ADC14/PCINT22)_83") (pintype "bidirectional"))
    )
    (net (code "107") (name "unconnected-(U1-PK7(ADC15{slash}PCINT23)-Pad82)") (class "Default")
      (node (ref "U1") (pin "82") (pinfunction "PK7(ADC15/PCINT23)_82") (pintype "bidirectional"))
    )
    (net (code "108") (name "unconnected-(U1-PL0(ICP4)-Pad35)") (class "Default")
      (node (ref "U1") (pin "35") (pinfunction "PL0(ICP4)_35") (pintype "bidirectional"))
    )
    (net (code "109") (name "unconnected-(U1-PL1(ICP5)-Pad36)") (class "Default")
      (node (ref "U1") (pin "36") (pinfunction "PL1(ICP5)_36") (pintype "bidirectional"))
    )
    (net (code "110") (name "unconnected-(U1-PL2(T5)-Pad37)") (class "Default")
      (node (ref "U1") (pin "37") (pinfunction "PL2(T5)_37") (pintype "bidirectional"))
    )
    (net (code "111") (name "unconnected-(U1-PL3(OC5A)-Pad38)") (class "Default")
      (node (ref "U1") (pin "38") (pinfunction "PL3(OC5A)_38") (pintype "bidirectional"))
    )
    (net (code "112") (name "unconnected-(U1-PL4(OC5B)-Pad39)") (class "Default")
      (node (ref "U1") (pin "39") (pinfunction "PL4(OC5B)_39") (pintype "bidirectional"))
    )
    (net (code "113") (name "unconnected-(U1-PL5(OC5C)-Pad40)") (class "Default")
      (node (ref "U1") (pin "40") (pinfunction "PL5(OC5C)_40") (pintype "bidirectional"))
    )
    (net (code "114") (name "unconnected-(U1-PL6-Pad41)") (class "Default")
      (node (ref "U1") (pin "41") (pinfunction "PL6_41") (pintype "bidirectional"))
    )
    (net (code "115") (name "unconnected-(U1-PL7-Pad42)") (class "Default")
      (node (ref "U1") (pin "42") (pinfunction "PL7_42") (pintype "bidirectional"))
    )
  )
)
